# schematic.net
KiCad netlist of a schematic drawn in EAGLE
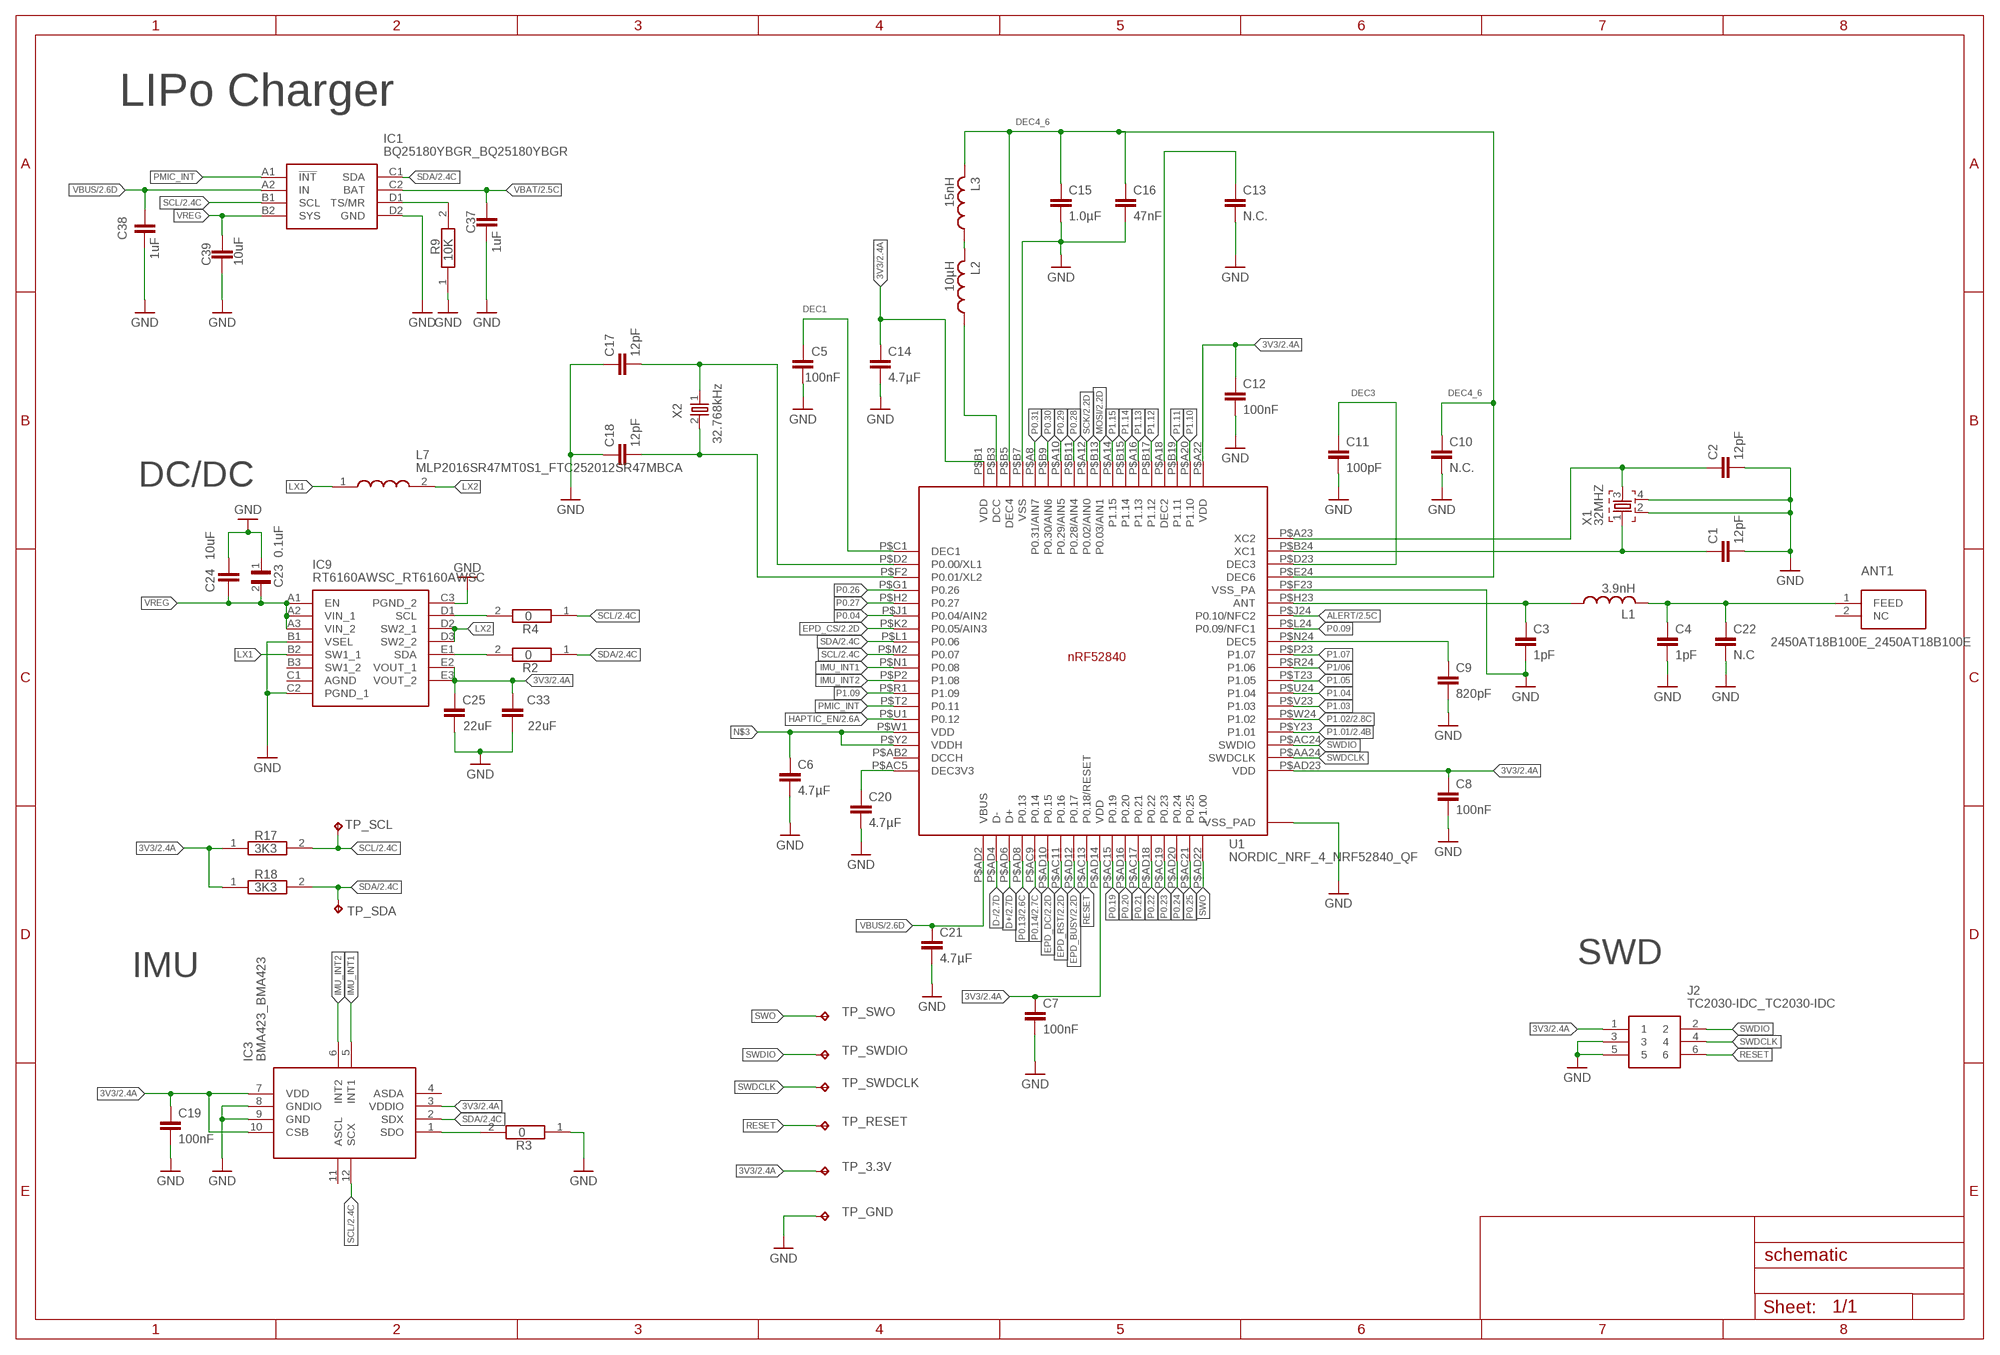
[diagram p0: schematic, sheet 1, part 1 of 2]
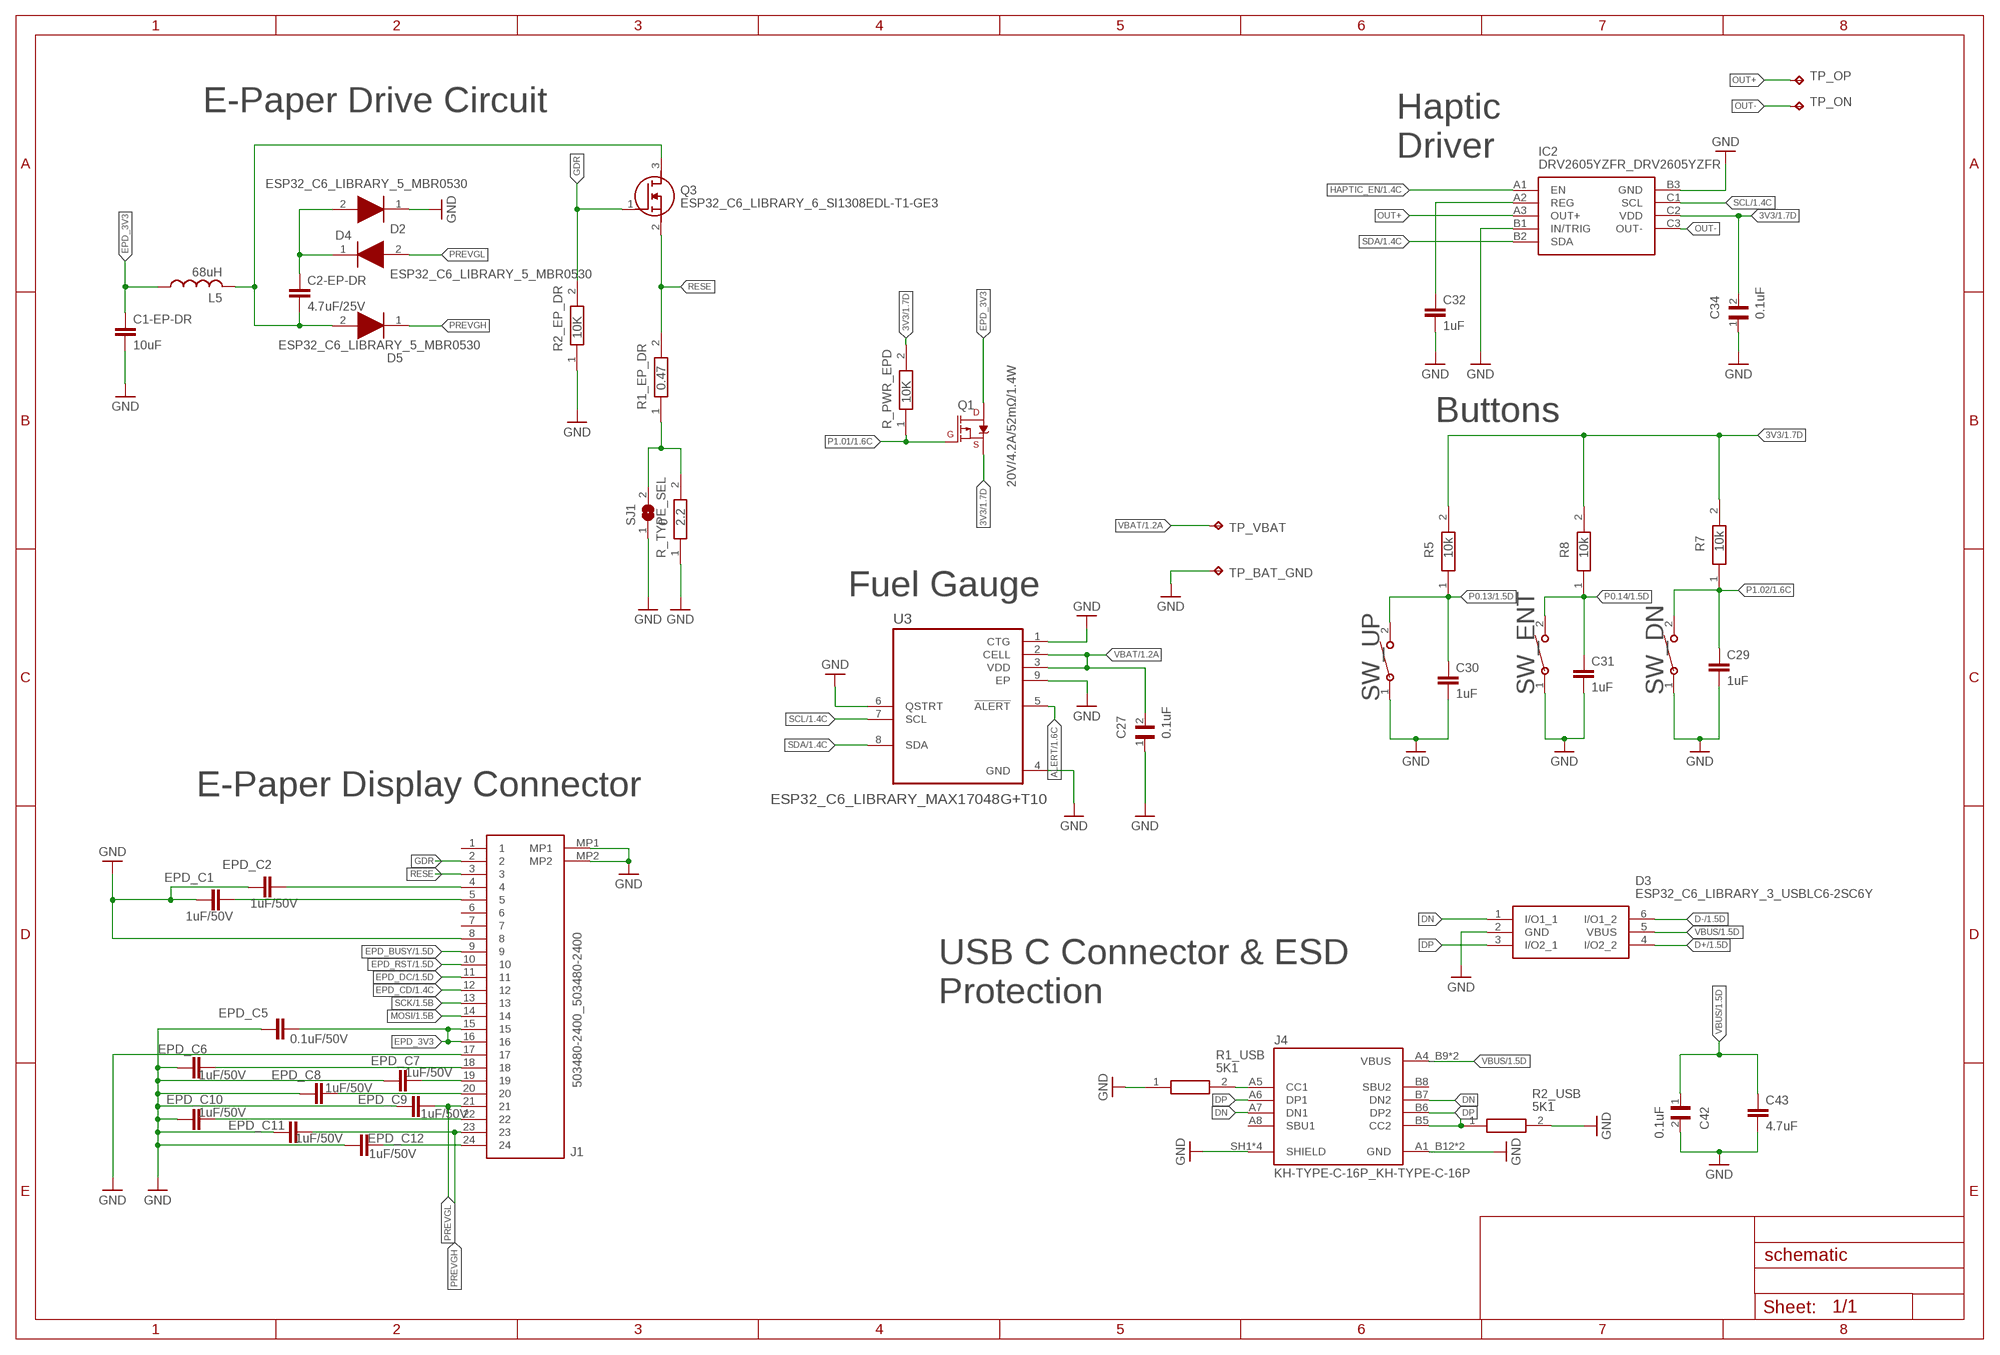
[diagram p1: schematic, sheet 1, part 2 of 2]

(export (version "E")
  (design (tool "Eeschema 10.0.6"))
  (components
    (comp (ref "ANT1")
      (value "2450AT18B100E_2450AT18B100E")
      (footprint "eagle-import:2450AT18B100E_ANTC3216X140N")
      (fields
        (field (name "ARROW_PART_NUMBER") "2450AT18B100E")
        (field (name "MOUSER_PART_NUMBER") "609-2450AT18B100E")
      )
      (libsource (lib "eagle-import") (part "2450AT18B100E_2450AT18B100E"))
    )
    (comp (ref "C1")
      (value "12pF")
      (footprint "eagle-import:NORDIC_NRF_3_RESC0201_L")
      (libsource (lib "eagle-import") (part "NORDIC_NRF_3_CAPACITOR_0201_L"))
    )
    (comp (ref "C1-EP-DR")
      (value "10uF")
      (footprint "eagle-import:PERFECT_0402_0402")
      (libsource (lib "eagle-import") (part "PERFECT_0402_CAP_0402"))
    )
    (comp (ref "C2")
      (value "12pF")
      (footprint "eagle-import:NORDIC_NRF_3_RESC0201_L")
      (libsource (lib "eagle-import") (part "NORDIC_NRF_3_CAPACITOR_0201_L"))
    )
    (comp (ref "C2-EP-DR")
      (value "4.7uF/25V")
      (footprint "eagle-import:PERFECT_0402_0402")
      (libsource (lib "eagle-import") (part "PERFECT_0402_CAP_0402"))
    )
    (comp (ref "C3")
      (value "1pF")
      (footprint "eagle-import:NORDIC_NRF_3_RESC0201_L")
      (libsource (lib "eagle-import") (part "NORDIC_NRF_3_CAPACITOR_0201_L"))
    )
    (comp (ref "C4")
      (value "1pF")
      (footprint "eagle-import:NORDIC_NRF_3_RESC0201_L")
      (libsource (lib "eagle-import") (part "NORDIC_NRF_3_CAPACITOR_0201_L"))
    )
    (comp (ref "C5")
      (value "100nF")
      (footprint "eagle-import:NORDIC_NRF_3_RESC0201_L")
      (libsource (lib "eagle-import") (part "NORDIC_NRF_3_CAPACITOR_0201_L"))
    )
    (comp (ref "C6")
      (value "4.7µF")
      (footprint "eagle-import:PERFECT_0402_0402")
      (libsource (lib "eagle-import") (part "PERFECT_0402_CAP_0402"))
    )
    (comp (ref "C7")
      (value "100nF")
      (footprint "eagle-import:PERFECT_0402_0402")
      (libsource (lib "eagle-import") (part "PERFECT_0402_CAP_0402"))
    )
    (comp (ref "C8")
      (value "100nF")
      (footprint "eagle-import:NORDIC_NRF_3_RESC0201_L")
      (libsource (lib "eagle-import") (part "NORDIC_NRF_3_CAPACITOR_0201_L"))
    )
    (comp (ref "C9")
      (value "820pF")
      (footprint "eagle-import:NORDIC_NRF_3_RESC0201_L")
      (libsource (lib "eagle-import") (part "NORDIC_NRF_3_CAPACITOR_0201_L"))
    )
    (comp (ref "C10")
      (value "N.C.")
      (footprint "eagle-import:NORDIC_NRF_3_RESC0201_L")
      (libsource (lib "eagle-import") (part "NORDIC_NRF_3_CAPACITOR_0201_L"))
    )
    (comp (ref "C11")
      (value "100pF")
      (footprint "eagle-import:NORDIC_NRF_3_RESC0201_L")
      (libsource (lib "eagle-import") (part "NORDIC_NRF_3_CAPACITOR_0201_L"))
    )
    (comp (ref "C12")
      (value "100nF")
      (footprint "eagle-import:NORDIC_NRF_3_RESC0201_L")
      (libsource (lib "eagle-import") (part "NORDIC_NRF_3_CAPACITOR_0201_L"))
    )
    (comp (ref "C13")
      (value "N.C.")
      (footprint "eagle-import:PERFECT_0402_0402")
      (libsource (lib "eagle-import") (part "PERFECT_0402_CAP_0402"))
    )
    (comp (ref "C14")
      (value "4.7µF")
      (footprint "eagle-import:PERFECT_0402_0402")
      (libsource (lib "eagle-import") (part "PERFECT_0402_CAP_0402"))
    )
    (comp (ref "C15")
      (value "1.0µF")
      (footprint "eagle-import:PERFECT_0402_0402")
      (libsource (lib "eagle-import") (part "PERFECT_0402_CAP_0402"))
    )
    (comp (ref "C16")
      (value "47nF")
      (footprint "eagle-import:NORDIC_NRF_3_RESC0201_L")
      (libsource (lib "eagle-import") (part "NORDIC_NRF_3_CAPACITOR_0201_L"))
    )
    (comp (ref "C17")
      (value "12pF")
      (footprint "eagle-import:NORDIC_NRF_3_RESC0201_L")
      (libsource (lib "eagle-import") (part "NORDIC_NRF_3_CAPACITOR_0201_L"))
    )
    (comp (ref "C18")
      (value "12pF")
      (footprint "eagle-import:NORDIC_NRF_3_RESC0201_L")
      (libsource (lib "eagle-import") (part "NORDIC_NRF_3_CAPACITOR_0201_L"))
    )
    (comp (ref "C19")
      (value "100nF")
      (footprint "eagle-import:NORDIC_NRF_3_RESC0201_L")
      (libsource (lib "eagle-import") (part "NORDIC_NRF_3_CAPACITOR_0201_L"))
    )
    (comp (ref "C20")
      (value "4.7µF")
      (footprint "eagle-import:PERFECT_0402_0402")
      (libsource (lib "eagle-import") (part "PERFECT_0402_CAP_0402"))
    )
    (comp (ref "C21")
      (value "4.7µF")
      (footprint "eagle-import:PERFECT_0402_0402")
      (libsource (lib "eagle-import") (part "PERFECT_0402_CAP_0402"))
    )
    (comp (ref "C22")
      (value "N.C")
      (footprint "eagle-import:NORDIC_NRF_3_RESC0201_L")
      (libsource (lib "eagle-import") (part "NORDIC_NRF_3_CAPACITOR_0201_L"))
    )
    (comp (ref "C23")
      (value "0.1uF")
      (footprint "eagle-import:GRM011R60J152KE01L_2_CAPC0201X13N")
      (fields (field (name "MF") "Murata") (field (name "MP") "GRM011R60J152KE01L"))
      (libsource (lib "eagle-import") (part "GRM011R60J152KE01L_2_GRM011R60J152KE01L"))
    )
    (comp (ref "C24")
      (value "10uF")
      (footprint "eagle-import:PERFECT_0402_0402")
      (libsource (lib "eagle-import") (part "PERFECT_0402_CAP_0402"))
    )
    (comp (ref "C25")
      (value "22uF")
      (footprint "eagle-import:PERFECT_0402_0402")
      (libsource (lib "eagle-import") (part "PERFECT_0402_CAP_0402"))
    )
    (comp (ref "C27")
      (value "0.1uF")
      (footprint "eagle-import:GRM011R60J152KE01L_2_CAPC0201X13N")
      (fields (field (name "MF") "Murata") (field (name "MP") "GRM011R60J152KE01L"))
      (libsource (lib "eagle-import") (part "GRM011R60J152KE01L_2_GRM011R60J152KE01L"))
    )
    (comp (ref "C29")
      (value "1uF")
      (footprint "eagle-import:PERFECT_0402_0402")
      (libsource (lib "eagle-import") (part "PERFECT_0402_CAP_0402"))
    )
    (comp (ref "C30")
      (value "1uF")
      (footprint "eagle-import:PERFECT_0402_0402")
      (libsource (lib "eagle-import") (part "PERFECT_0402_CAP_0402"))
    )
    (comp (ref "C31")
      (value "1uF")
      (footprint "eagle-import:PERFECT_0402_0402")
      (libsource (lib "eagle-import") (part "PERFECT_0402_CAP_0402"))
    )
    (comp (ref "C32")
      (value "1uF")
      (footprint "eagle-import:PERFECT_0402_0402")
      (libsource (lib "eagle-import") (part "PERFECT_0402_CAP_0402"))
    )
    (comp (ref "C33")
      (value "22uF")
      (footprint "eagle-import:PERFECT_0402_0402")
      (libsource (lib "eagle-import") (part "PERFECT_0402_CAP_0402"))
    )
    (comp (ref "C34")
      (value "0.1uF")
      (footprint "eagle-import:GRM011R60J152KE01L_2_CAPC0201X13N")
      (fields (field (name "MF") "Murata") (field (name "MP") "GRM011R60J152KE01L"))
      (libsource (lib "eagle-import") (part "GRM011R60J152KE01L_2_GRM011R60J152KE01L"))
    )
    (comp (ref "C37")
      (value "1uF")
      (footprint "eagle-import:PERFECT_0402_0402")
      (libsource (lib "eagle-import") (part "PERFECT_0402_CAP_0402"))
    )
    (comp (ref "C38")
      (value "1uF")
      (footprint "eagle-import:PERFECT_0402_0402")
      (libsource (lib "eagle-import") (part "PERFECT_0402_CAP_0402"))
    )
    (comp (ref "C39")
      (value "10uF")
      (footprint "eagle-import:PERFECT_0402_0402")
      (libsource (lib "eagle-import") (part "PERFECT_0402_CAP_0402"))
    )
    (comp (ref "C42")
      (value "0.1uF")
      (footprint "eagle-import:GRM011R60J152KE01L_2_CAPC0201X13N")
      (fields (field (name "MF") "Murata") (field (name "MP") "GRM011R60J152KE01L"))
      (libsource (lib "eagle-import") (part "GRM011R60J152KE01L_2_GRM011R60J152KE01L"))
    )
    (comp (ref "C43")
      (value "4.7uF")
      (footprint "eagle-import:PERFECT_0402_0402")
      (libsource (lib "eagle-import") (part "PERFECT_0402_CAP_0402"))
    )
    (comp (ref "D2")
      (value "ESP32_C6_LIBRARY_5_MBR0530")
      (footprint "eagle-import:ESP32_C6_LIBRARY_5_SOD3716X135N")
      (fields (field (name "MF") "ON Semiconductor") (field (name "MP") "MBR0530"))
      (libsource (lib "eagle-import") (part "ESP32_C6_LIBRARY_5_MBR0530"))
    )
    (comp (ref "D3")
      (value "ESP32_C6_LIBRARY_3_USBLC6-2SC6Y")
      (footprint "eagle-import:ESP32_C6_LIBRARY_3_SOT95P280X145-6N")
      (fields (field (name "MF") "STMicroelectronics") (field (name "MP") "USBLC6-2SC6Y"))
      (libsource (lib "eagle-import") (part "ESP32_C6_LIBRARY_3_USBLC6-2SC6Y"))
    )
    (comp (ref "D4")
      (value "ESP32_C6_LIBRARY_5_MBR0530")
      (footprint "eagle-import:ESP32_C6_LIBRARY_5_SOD3716X135N")
      (fields (field (name "MF") "ON Semiconductor") (field (name "MP") "MBR0530"))
      (libsource (lib "eagle-import") (part "ESP32_C6_LIBRARY_5_MBR0530"))
    )
    (comp (ref "D5")
      (value "ESP32_C6_LIBRARY_5_MBR0530")
      (footprint "eagle-import:ESP32_C6_LIBRARY_5_SOD3716X135N")
      (fields (field (name "MF") "ON Semiconductor") (field (name "MP") "MBR0530"))
      (libsource (lib "eagle-import") (part "ESP32_C6_LIBRARY_5_MBR0530"))
    )
    (comp (ref "EPD_C1")
      (value "1uF/50V")
      (footprint "eagle-import:PERFECT_0402_0402")
      (libsource (lib "eagle-import") (part "PERFECT_0402_CAP_0402"))
    )
    (comp (ref "EPD_C2")
      (value "1uF/50V")
      (footprint "eagle-import:PERFECT_0402_0402")
      (libsource (lib "eagle-import") (part "PERFECT_0402_CAP_0402"))
    )
    (comp (ref "EPD_C5")
      (value "0.1uF/50V")
      (footprint "eagle-import:NORDIC_NRF_3_RESC0201_L")
      (libsource (lib "eagle-import") (part "NORDIC_NRF_3_CAPACITOR_0201_L"))
    )
    (comp (ref "EPD_C6")
      (value "1uF/50V")
      (footprint "eagle-import:PERFECT_0402_0402")
      (libsource (lib "eagle-import") (part "PERFECT_0402_CAP_0402"))
    )
    (comp (ref "EPD_C7")
      (value "1uF/50V")
      (footprint "eagle-import:PERFECT_0402_0402")
      (libsource (lib "eagle-import") (part "PERFECT_0402_CAP_0402"))
    )
    (comp (ref "EPD_C8")
      (value "1uF/50V")
      (footprint "eagle-import:PERFECT_0402_0402")
      (libsource (lib "eagle-import") (part "PERFECT_0402_CAP_0402"))
    )
    (comp (ref "EPD_C9")
      (value "1uF/50V")
      (footprint "eagle-import:PERFECT_0402_0402")
      (libsource (lib "eagle-import") (part "PERFECT_0402_CAP_0402"))
    )
    (comp (ref "EPD_C10")
      (value "1uF/50V")
      (footprint "eagle-import:PERFECT_0402_0402")
      (libsource (lib "eagle-import") (part "PERFECT_0402_CAP_0402"))
    )
    (comp (ref "EPD_C11")
      (value "1uF/50V")
      (footprint "eagle-import:PERFECT_0402_0402")
      (libsource (lib "eagle-import") (part "PERFECT_0402_CAP_0402"))
    )
    (comp (ref "EPD_C12")
      (value "1uF/50V")
      (footprint "eagle-import:PERFECT_0402_0402")
      (libsource (lib "eagle-import") (part "PERFECT_0402_CAP_0402"))
    )
    (comp (ref "IC1")
      (value "BQ25180YBGR_BQ25180YBGR")
      (footprint "eagle-import:BQ25180YBGR_BGA8C40P2X4_100X155X50")
      (fields
        (field (name "ARROW_PART_NUMBER") "BQ25180YBGR")
        (field (name "MOUSER_PART_NUMBER") "595-BQ25180YBGR")
      )
      (libsource (lib "eagle-import") (part "BQ25180YBGR_BQ25180YBGR"))
    )
    (comp (ref "IC2")
      (value "DRV2605YZFR_DRV2605YZFR")
      (footprint "eagle-import:DRV2605YZFR_BGA9C50P3X3_144X144X62")
      (fields (field (name "ARROW_PART_NUMBER") "DRV2605YZFR"))
      (libsource (lib "eagle-import") (part "DRV2605YZFR_DRV2605YZFR"))
    )
    (comp (ref "IC3")
      (value "BMA423_BMA423")
      (footprint "eagle-import:BMA423_BMA423")
      (fields (field (name "ARROW_PART_NUMBER") "BMA423") (field (name "MOUSER_PART_NUMBER") "262-BMA423"))
      (libsource (lib "eagle-import") (part "BMA423_BMA423"))
    )
    (comp (ref "IC9")
      (value "RT6160AWSC_RT6160AWSC")
      (footprint "eagle-import:RT6160AWSC_BGA15C40P3X5_140X230X60")
      (fields
        (field (name "MANUFACTURER_PART_NUMBER") "RT6160AWSC")
        (field (name "MOUSER_PART_NUMBER") "835-RT6160AWSC")
      )
      (libsource (lib "eagle-import") (part "RT6160AWSC_RT6160AWSC"))
    )
    (comp (ref "J1")
      (value "503480-2400_503480-2400")
      (footprint "eagle-import:503480-2400_5034802400")
      (fields
        (field (name "MANUFACTURER_PART_NUMBER") "503480-2400")
        (field (name "MOUSER_PART_NUMBER") "538-503480-2400")
      )
      (libsource (lib "eagle-import") (part "503480-2400_503480-2400"))
    )
    (comp (ref "J2")
      (value "TC2030-IDC_TC2030-IDC")
      (footprint "eagle-import:TC2030-IDC_TC2030IDC")
      (fields (field (name "MANUFACTURER_PART_NUMBER") "TC2030-IDC"))
      (libsource (lib "eagle-import") (part "TC2030-IDC_TC2030-IDC"))
    )
    (comp (ref "J4")
      (value "KH-TYPE-C-16P_KH-TYPE-C-16P")
      (footprint "eagle-import:KH-TYPE-C-16P_KINGHELM_KH-TYPE-C-16P")
      (fields (field (name "MF") "kinghelm") (field (name "MP") "KH-TYPE-C-16P"))
      (libsource (lib "eagle-import") (part "KH-TYPE-C-16P_KH-TYPE-C-16P"))
    )
    (comp (ref "L1")
      (value "3.9nH")
      (footprint "eagle-import:NORDIC_NRF_2_RESC0402_L")
      (libsource (lib "eagle-import") (part "NORDIC_NRF_2_INDUCTOR_0402_L"))
    )
    (comp (ref "L2")
      (value "10µH")
      (footprint "eagle-import:NORDIC_NRF_2_RESC0402_L")
      (libsource (lib "eagle-import") (part "NORDIC_NRF_2_INDUCTOR_0402_L"))
    )
    (comp (ref "L3")
      (value "15nH")
      (footprint "eagle-import:NORDIC_NRF_2_RESC0402_L")
      (libsource (lib "eagle-import") (part "NORDIC_NRF_2_INDUCTOR_0402_L"))
    )
    (comp (ref "L5")
      (value "68uH")
      (footprint "eagle-import:NORDIC_NRF_2_RESC0402_L")
      (libsource (lib "eagle-import") (part "NORDIC_NRF_2_INDUCTOR_0402_L"))
    )
    (comp (ref "L7")
      (value "MLP2016SR47MT0S1_FTC252012SR47MBCA")
      (footprint "eagle-import:MLP2016SR47MT0S1_INDC2016X100N")
      (fields (field (name "MANUFACTURER_PART_NUMBER") "FTC252012SR47MBCA"))
      (libsource (lib "eagle-import") (part "MLP2016SR47MT0S1_FTC252012SR47MBCA"))
    )
    (comp (ref "Q1")
      (value "20V/4.2A/52mΩ/1.4W")
      (footprint "eagle-import:ESP32_C6_LIBRARY_4_ESP32_C6_LIBRARY_4_ESP32_C6_LIBRARY_4_ESP32_C6_LIBRARY_4_ESP32_WROVER_SPARKFUN-DISCRETESEMI_SOT23-3")
      (libsource (lib "eagle-import") (part "ESP32_C6_LIBRARY_4_ESP32_WROVER_SPARKFUN-DISCRETESEMI_MOSFET_PCH-DMG2305UX-7"))
    )
    (comp (ref "Q3")
      (value "ESP32_C6_LIBRARY_6_SI1308EDL-T1-GE3")
      (footprint "eagle-import:ESP32_C6_LIBRARY_6_SOT65P210X110-3N")
      (fields (field (name "MF") "Vishay Siliconix") (field (name "MP") "SI1308EDL-T1-GE3"))
      (libsource (lib "eagle-import") (part "ESP32_C6_LIBRARY_6_SI1308EDL-T1-GE3"))
    )
    (comp (ref "R1_EP_DR")
      (value "0.47")
      (footprint "eagle-import:CPF0201D7K68C1_0201")
      (libsource (lib "eagle-import") (part "CPF0201D7K68C1_CPF0201D7K68C1"))
    )
    (comp (ref "R1_USB")
      (value "5K1")
      (footprint "eagle-import:CPF0201D7K68C1_0201")
      (libsource (lib "eagle-import") (part "CPF0201D7K68C1_CPF0201D7K68C1"))
    )
    (comp (ref "R2")
      (value "0")
      (footprint "eagle-import:ERA-1AEB3401C_0201")
      (libsource (lib "eagle-import") (part "ERA-1AEB3401C_CPF0201D7K68C1"))
    )
    (comp (ref "R2_EP_DR")
      (value "10K")
      (footprint "eagle-import:CPF0201D7K68C1_0201")
      (libsource (lib "eagle-import") (part "CPF0201D7K68C1_CPF0201D7K68C1"))
    )
    (comp (ref "R2_USB")
      (value "5K1")
      (footprint "eagle-import:CPF0201D7K68C1_0201")
      (libsource (lib "eagle-import") (part "CPF0201D7K68C1_CPF0201D7K68C1"))
    )
    (comp (ref "R3")
      (value "0")
      (footprint "eagle-import:ERA-1AEB3401C_0201")
      (libsource (lib "eagle-import") (part "ERA-1AEB3401C_CPF0201D7K68C1"))
    )
    (comp (ref "R4")
      (value "0")
      (footprint "eagle-import:ERA-1AEB3401C_0201")
      (libsource (lib "eagle-import") (part "ERA-1AEB3401C_CPF0201D7K68C1"))
    )
    (comp (ref "R5")
      (value "10k")
      (footprint "eagle-import:CPF0201D7K68C1_0201")
      (libsource (lib "eagle-import") (part "CPF0201D7K68C1_CPF0201D7K68C1"))
    )
    (comp (ref "R7")
      (value "10k")
      (footprint "eagle-import:CPF0201D7K68C1_0201")
      (libsource (lib "eagle-import") (part "CPF0201D7K68C1_CPF0201D7K68C1"))
    )
    (comp (ref "R8")
      (value "10k")
      (footprint "eagle-import:CPF0201D7K68C1_0201")
      (libsource (lib "eagle-import") (part "CPF0201D7K68C1_CPF0201D7K68C1"))
    )
    (comp (ref "R9")
      (value "10K")
      (footprint "eagle-import:CPF0201D7K68C1_0201")
      (libsource (lib "eagle-import") (part "CPF0201D7K68C1_CPF0201D7K68C1"))
    )
    (comp (ref "R17")
      (value "3K3")
      (footprint "eagle-import:ERA-1AEB3401C_0201")
      (libsource (lib "eagle-import") (part "ERA-1AEB3401C_CPF0201D7K68C1"))
    )
    (comp (ref "R18")
      (value "3K3")
      (footprint "eagle-import:ERA-1AEB3401C_0201")
      (libsource (lib "eagle-import") (part "ERA-1AEB3401C_CPF0201D7K68C1"))
    )
    (comp (ref "R_PWR_EPD")
      (value "10K")
      (footprint "eagle-import:CPF0201D7K68C1_0201")
      (libsource (lib "eagle-import") (part "CPF0201D7K68C1_CPF0201D7K68C1"))
    )
    (comp (ref "R_TYPE_SEL")
      (value "2.2")
      (footprint "eagle-import:CPF0201D7K68C1_0201")
      (libsource (lib "eagle-import") (part "CPF0201D7K68C1_CPF0201D7K68C1"))
    )
    (comp (ref "SJ1")
      (value "0")
      (footprint "eagle-import:ESP32_C6_LIBRARY_7_JUMPER_SJ")
      (libsource (lib "eagle-import") (part "ESP32_C6_LIBRARY_7_JUMPER_SJ"))
    )
    (comp (ref "SW_DN")
      (value "2025-10-22_07-23-44_LIBRARY_EVP-AKE31ASW_EVP-AKE31A_PAN")
      (footprint "eagle-import:2025-10-22_07-23-44_LIBRARY_SW_EVP-AKE31A_PAN")
      (fields
        (field (name "MANUFACTURER_PART_NUMBER") "EVP-AKE31A")
        (field (name "COPYRIGHT") "Copyright (C) 2025 Ultra Librarian. All rights reserved.")
      )
      (libsource (lib "eagle-import") (part "2025-10-22_07-23-44_LIBRARY_EVP-AKE31ASW_EVP-AKE31A_PAN"))
    )
    (comp (ref "SW_ENT")
      (value "2025-10-22_07-23-44_LIBRARY_EVP-AKE31ASW_EVP-AKE31A_PAN")
      (footprint "eagle-import:2025-10-22_07-23-44_LIBRARY_SW_EVP-AKE31A_PAN")
      (fields
        (field (name "MANUFACTURER_PART_NUMBER") "EVP-AKE31A")
        (field (name "COPYRIGHT") "Copyright (C) 2025 Ultra Librarian. All rights reserved.")
      )
      (libsource (lib "eagle-import") (part "2025-10-22_07-23-44_LIBRARY_EVP-AKE31ASW_EVP-AKE31A_PAN"))
    )
    (comp (ref "SW_UP")
      (value "2025-10-22_07-23-44_LIBRARY_EVP-AKE31ASW_EVP-AKE31A_PAN")
      (footprint "eagle-import:2025-10-22_07-23-44_LIBRARY_SW_EVP-AKE31A_PAN")
      (fields
        (field (name "MANUFACTURER_PART_NUMBER") "EVP-AKE31A")
        (field (name "COPYRIGHT") "Copyright (C) 2025 Ultra Librarian. All rights reserved.")
      )
      (libsource (lib "eagle-import") (part "2025-10-22_07-23-44_LIBRARY_EVP-AKE31ASW_EVP-AKE31A_PAN"))
    )
    (comp (ref "TP_3.3V")
      (value "HECTOR_WATCH_1_TPTP20R")
      (footprint "eagle-import:HECTOR_WATCH_1_TP20R")
      (libsource (lib "eagle-import") (part "HECTOR_WATCH_1_TPTP20R"))
    )
    (comp (ref "TP_BAT_GND")
      (value "HECTOR_WATCH_1_TPTP20R")
      (footprint "eagle-import:HECTOR_WATCH_1_TP20R")
      (libsource (lib "eagle-import") (part "HECTOR_WATCH_1_TPTP20R"))
    )
    (comp (ref "TP_GND")
      (value "HECTOR_WATCH_1_TPTP20R")
      (footprint "eagle-import:HECTOR_WATCH_1_TP20R")
      (libsource (lib "eagle-import") (part "HECTOR_WATCH_1_TPTP20R"))
    )
    (comp (ref "TP_ON")
      (value "HECTOR_WATCH_1_TPTP20R")
      (footprint "eagle-import:HECTOR_WATCH_1_TP20R")
      (libsource (lib "eagle-import") (part "HECTOR_WATCH_1_TPTP20R"))
    )
    (comp (ref "TP_OP")
      (value "HECTOR_WATCH_1_TPTP20R")
      (footprint "eagle-import:HECTOR_WATCH_1_TP20R")
      (libsource (lib "eagle-import") (part "HECTOR_WATCH_1_TPTP20R"))
    )
    (comp (ref "TP_RESET")
      (value "HECTOR_WATCH_1_TPTP20R")
      (footprint "eagle-import:HECTOR_WATCH_1_TP20R")
      (libsource (lib "eagle-import") (part "HECTOR_WATCH_1_TPTP20R"))
    )
    (comp (ref "TP_SCL")
      (value "HECTOR_WATCH_1_TPTP20R")
      (footprint "eagle-import:HECTOR_WATCH_1_TP20R")
      (libsource (lib "eagle-import") (part "HECTOR_WATCH_1_TPTP20R"))
    )
    (comp (ref "TP_SDA")
      (value "HECTOR_WATCH_1_TPTP20R")
      (footprint "eagle-import:HECTOR_WATCH_1_TP20R")
      (libsource (lib "eagle-import") (part "HECTOR_WATCH_1_TPTP20R"))
    )
    (comp (ref "TP_SWDCLK")
      (value "HECTOR_WATCH_1_TPTP20R")
      (footprint "eagle-import:HECTOR_WATCH_1_TP20R")
      (libsource (lib "eagle-import") (part "HECTOR_WATCH_1_TPTP20R"))
    )
    (comp (ref "TP_SWDIO")
      (value "HECTOR_WATCH_1_TPTP20R")
      (footprint "eagle-import:HECTOR_WATCH_1_TP20R")
      (libsource (lib "eagle-import") (part "HECTOR_WATCH_1_TPTP20R"))
    )
    (comp (ref "TP_SWO")
      (value "HECTOR_WATCH_1_TPTP20R")
      (footprint "eagle-import:HECTOR_WATCH_1_TP20R")
      (libsource (lib "eagle-import") (part "HECTOR_WATCH_1_TPTP20R"))
    )
    (comp (ref "TP_VBAT")
      (value "HECTOR_WATCH_1_TPTP20R")
      (footprint "eagle-import:HECTOR_WATCH_1_TP20R")
      (libsource (lib "eagle-import") (part "HECTOR_WATCH_1_TPTP20R"))
    )
    (comp (ref "U1")
      (value "NORDIC_NRF_4_NRF52840_QF")
      (footprint "eagle-import:NORDIC_NRF_4_AQFN50P700X700X85_HS-74N")
      (libsource (lib "eagle-import") (part "NORDIC_NRF_4_NRF52840_QF"))
    )
    (comp (ref "U3")
      (value "ESP32_C6_LIBRARY_MAX17048G+T10")
      (footprint "eagle-import:ESP32_C6_LIBRARY_SON50P200X200X80-9N")
      (fields (field (name "MF") "Analog Devices") (field (name "MP") "MAX17048G+T10"))
      (libsource (lib "eagle-import") (part "ESP32_C6_LIBRARY_MAX17048G+T10"))
    )
    (comp (ref "X1")
      (value "32MHZ")
      (footprint "eagle-import:NORDIC_NRF_BT-XTAL_2016_N")
      (libsource (lib "eagle-import") (part "NORDIC_NRF_XTAL_32MHZ"))
    )
    (comp (ref "X2")
      (value "32.768kHz")
      (footprint "eagle-import:NORDIC_NRF_1_XTAL_3215_N")
      (libsource (lib "eagle-import") (part "NORDIC_NRF_1_XTAL_32KHZ"))
    )
  )
  (nets
    (net (code "1") (name "3V3{slash}1.7D") (class "Default")
      (node (ref "C34") (pin "2") (pinfunction "2_2") (pintype "passive"))
      (node (ref "IC2") (pin "C2") (pinfunction "VDD_C2") (pintype "bidirectional"))
      (node (ref "Q1") (pin "2") (pinfunction "S_2") (pintype "bidirectional"))
      (node (ref "R5") (pin "2") (pinfunction "2_2") (pintype "bidirectional"))
      (node (ref "R7") (pin "2") (pinfunction "2_2") (pintype "bidirectional"))
      (node (ref "R8") (pin "2") (pinfunction "2_2") (pintype "bidirectional"))
      (node (ref "R_PWR_EPD") (pin "2") (pinfunction "2_2") (pintype "bidirectional"))
    )
    (net (code "2") (name "3V3{slash}2.4A") (class "Default")
      (node (ref "C12") (pin "1") (pinfunction "1_1") (pintype "passive"))
      (node (ref "C14") (pin "1") (pinfunction "1_1") (pintype "passive"))
      (node (ref "C19") (pin "1") (pinfunction "1_1") (pintype "passive"))
      (node (ref "C25") (pin "2") (pinfunction "2_2") (pintype "passive"))
      (node (ref "C33") (pin "2") (pinfunction "2_2") (pintype "passive"))
      (node (ref "C7") (pin "1") (pinfunction "1_1") (pintype "passive"))
      (node (ref "C8") (pin "1") (pinfunction "1_1") (pintype "passive"))
      (node (ref "IC3") (pin "10") (pinfunction "CSB_10") (pintype "bidirectional"))
      (node (ref "IC3") (pin "3") (pinfunction "VDDIO_3") (pintype "bidirectional"))
      (node (ref "IC3") (pin "7") (pinfunction "VDD_7") (pintype "bidirectional"))
      (node (ref "IC9") (pin "E2") (pinfunction "VOUT_1_E2") (pintype "bidirectional"))
      (node (ref "IC9") (pin "E3") (pinfunction "VOUT_2_E3") (pintype "bidirectional"))
      (node (ref "J2") (pin "1") (pinfunction "1_1") (pintype "bidirectional"))
      (node (ref "R17") (pin "1") (pinfunction "1_1") (pintype "bidirectional"))
      (node (ref "R18") (pin "1") (pinfunction "1_1") (pintype "bidirectional"))
      (node (ref "TP_3.3V") (pin "TP") (pinfunction "TP_TP") (pintype "input"))
      (node (ref "U1") (pin "P$A22") (pinfunction "VDD_P$A22") (pintype "power_in"))
      (node (ref "U1") (pin "P$AD14") (pinfunction "VDD_P$AD14") (pintype "power_in"))
      (node (ref "U1") (pin "P$AD23") (pinfunction "VDD_P$AD23") (pintype "power_in"))
      (node (ref "U1") (pin "P$B1") (pinfunction "VDD_P$B1") (pintype "power_in"))
    )
    (net (code "3") (name "ALERT{slash}1.6C") (class "Default")
      (node (ref "U3") (pin "5") (pinfunction "~{ALERT}_5") (pintype "output"))
    )
    (net (code "4") (name "ALERT{slash}2.5C") (class "Default")
      (node (ref "U1") (pin "P$J24") (pinfunction "P0.10/NFC2_P$J24") (pintype "bidirectional"))
    )
    (net (code "5") (name "D+{slash}1.5D") (class "Default")
      (node (ref "D3") (pin "4") (pinfunction "I/O2_2_4") (pintype "bidirectional"))
    )
    (net (code "6") (name "D+{slash}2.7D") (class "Default")
      (node (ref "U1") (pin "P$AD6") (pinfunction "D+_P$AD6") (pintype "bidirectional"))
    )
    (net (code "7") (name "D-{slash}1.5D") (class "Default")
      (node (ref "D3") (pin "6") (pinfunction "I/O1_2_6") (pintype "bidirectional"))
    )
    (net (code "8") (name "D-{slash}2.7D") (class "Default")
      (node (ref "U1") (pin "P$AD4") (pinfunction "D-_P$AD4") (pintype "bidirectional"))
    )
    (net (code "9") (name "DN") (class "Default")
      (node (ref "D3") (pin "1") (pinfunction "I/O1_1_1") (pintype "bidirectional"))
      (node (ref "J4") (pin "A7") (pinfunction "DN1_A7") (pintype "bidirectional"))
      (node (ref "J4") (pin "B7") (pinfunction "DN2_B7") (pintype "bidirectional"))
    )
    (net (code "10") (name "DP") (class "Default")
      (node (ref "D3") (pin "3") (pinfunction "I/O2_1_3") (pintype "bidirectional"))
      (node (ref "J4") (pin "A6") (pinfunction "DP1_A6") (pintype "bidirectional"))
      (node (ref "J4") (pin "B6") (pinfunction "DP2_B6") (pintype "bidirectional"))
    )
    (net (code "11") (name "EPD_3V3") (class "Default")
      (node (ref "C1-EP-DR") (pin "1") (pinfunction "1_1") (pintype "passive"))
      (node (ref "EPD_C5") (pin "2") (pinfunction "2_2") (pintype "passive"))
      (node (ref "J1") (pin "15") (pinfunction "15_15") (pintype "bidirectional"))
      (node (ref "J1") (pin "16") (pinfunction "16_16") (pintype "bidirectional"))
      (node (ref "L5") (pin "1") (pinfunction "1_1") (pintype "passive"))
      (node (ref "Q1") (pin "3") (pinfunction "D_3") (pintype "bidirectional"))
    )
    (net (code "12") (name "EPD_BUSY{slash}1.5D") (class "Default")
      (node (ref "J1") (pin "9") (pinfunction "9_9") (pintype "bidirectional"))
    )
    (net (code "13") (name "EPD_BUSY{slash}2.2D") (class "Default")
      (node (ref "U1") (pin "P$AC11") (pinfunction "P0.16_P$AC11") (pintype "bidirectional"))
    )
    (net (code "14") (name "EPD_CD{slash}1.4C") (class "Default")
      (node (ref "J1") (pin "12") (pinfunction "12_12") (pintype "bidirectional"))
    )
    (net (code "15") (name "EPD_CS{slash}2.2D") (class "Default")
      (node (ref "U1") (pin "P$K2") (pinfunction "P0.05/AIN3_P$K2") (pintype "bidirectional"))
    )
    (net (code "16") (name "EPD_DC{slash}1.5D") (class "Default")
      (node (ref "J1") (pin "11") (pinfunction "11_11") (pintype "bidirectional"))
    )
    (net (code "17") (name "EPD_DC{slash}2.2D") (class "Default")
      (node (ref "U1") (pin "P$AD10") (pinfunction "P0.15_P$AD10") (pintype "bidirectional"))
    )
    (net (code "18") (name "EPD_RST{slash}1.5D") (class "Default")
      (node (ref "J1") (pin "10") (pinfunction "10_10") (pintype "bidirectional"))
    )
    (net (code "19") (name "EPD_RST{slash}2.2D") (class "Default")
      (node (ref "U1") (pin "P$AD12") (pinfunction "P0.17_P$AD12") (pintype "bidirectional"))
    )
    (net (code "20") (name "GDR") (class "Default")
      (node (ref "J1") (pin "2") (pinfunction "2_2") (pintype "bidirectional"))
      (node (ref "Q3") (pin "1") (pinfunction "G_1") (pintype "bidirectional"))
      (node (ref "R2_EP_DR") (pin "2") (pinfunction "2_2") (pintype "bidirectional"))
    )
    (net (code "21") (name "GND") (class "Default")
      (node (ref "C1") (pin "2") (pinfunction "2_2") (pintype "passive"))
      (node (ref "C1-EP-DR") (pin "2") (pinfunction "2_2") (pintype "passive"))
      (node (ref "C10") (pin "2") (pinfunction "2_2") (pintype "passive"))
      (node (ref "C11") (pin "2") (pinfunction "2_2") (pintype "passive"))
      (node (ref "C12") (pin "2") (pinfunction "2_2") (pintype "passive"))
      (node (ref "C13") (pin "2") (pinfunction "2_2") (pintype "passive"))
      (node (ref "C14") (pin "2") (pinfunction "2_2") (pintype "passive"))
      (node (ref "C15") (pin "2") (pinfunction "2_2") (pintype "passive"))
      (node (ref "C16") (pin "2") (pinfunction "2_2") (pintype "passive"))
      (node (ref "C17") (pin "1") (pinfunction "1_1") (pintype "passive"))
      (node (ref "C18") (pin "1") (pinfunction "1_1") (pintype "passive"))
      (node (ref "C19") (pin "2") (pinfunction "2_2") (pintype "passive"))
      (node (ref "C2") (pin "2") (pinfunction "2_2") (pintype "passive"))
      (node (ref "C20") (pin "2") (pinfunction "2_2") (pintype "passive"))
      (node (ref "C21") (pin "2") (pinfunction "2_2") (pintype "passive"))
      (node (ref "C22") (pin "2") (pinfunction "2_2") (pintype "passive"))
      (node (ref "C23") (pin "1") (pinfunction "1_1") (pintype "passive"))
      (node (ref "C24") (pin "2") (pinfunction "2_2") (pintype "passive"))
      (node (ref "C25") (pin "1") (pinfunction "1_1") (pintype "passive"))
      (node (ref "C27") (pin "1") (pinfunction "1_1") (pintype "passive"))
      (node (ref "C29") (pin "2") (pinfunction "2_2") (pintype "passive"))
      (node (ref "C3") (pin "2") (pinfunction "2_2") (pintype "passive"))
      (node (ref "C30") (pin "2") (pinfunction "2_2") (pintype "passive"))
      (node (ref "C31") (pin "2") (pinfunction "2_2") (pintype "passive"))
      (node (ref "C32") (pin "2") (pinfunction "2_2") (pintype "passive"))
      (node (ref "C33") (pin "1") (pinfunction "1_1") (pintype "passive"))
      (node (ref "C34") (pin "1") (pinfunction "1_1") (pintype "passive"))
      (node (ref "C37") (pin "2") (pinfunction "2_2") (pintype "passive"))
      (node (ref "C38") (pin "2") (pinfunction "2_2") (pintype "passive"))
      (node (ref "C39") (pin "2") (pinfunction "2_2") (pintype "passive"))
      (node (ref "C4") (pin "2") (pinfunction "2_2") (pintype "passive"))
      (node (ref "C42") (pin "2") (pinfunction "2_2") (pintype "passive"))
      (node (ref "C43") (pin "2") (pinfunction "2_2") (pintype "passive"))
      (node (ref "C5") (pin "1") (pinfunction "1_1") (pintype "passive"))
      (node (ref "C6") (pin "2") (pinfunction "2_2") (pintype "passive"))
      (node (ref "C7") (pin "2") (pinfunction "2_2") (pintype "passive"))
      (node (ref "C8") (pin "2") (pinfunction "2_2") (pintype "passive"))
      (node (ref "C9") (pin "2") (pinfunction "2_2") (pintype "passive"))
      (node (ref "D3") (pin "2") (pinfunction "GND_2") (pintype "bidirectional"))
      (node (ref "D4") (pin "1") (pinfunction "K_1") (pintype "bidirectional"))
      (node (ref "EPD_C1") (pin "1") (pinfunction "1_1") (pintype "passive"))
      (node (ref "EPD_C10") (pin "1") (pinfunction "1_1") (pintype "passive"))
      (node (ref "EPD_C11") (pin "1") (pinfunction "1_1") (pintype "passive"))
      (node (ref "EPD_C12") (pin "1") (pinfunction "1_1") (pintype "passive"))
      (node (ref "EPD_C2") (pin "1") (pinfunction "1_1") (pintype "passive"))
      (node (ref "EPD_C5") (pin "1") (pinfunction "1_1") (pintype "passive"))
      (node (ref "EPD_C6") (pin "1") (pinfunction "1_1") (pintype "passive"))
      (node (ref "EPD_C7") (pin "1") (pinfunction "1_1") (pintype "passive"))
      (node (ref "EPD_C8") (pin "1") (pinfunction "1_1") (pintype "passive"))
      (node (ref "EPD_C9") (pin "1") (pinfunction "1_1") (pintype "passive"))
      (node (ref "IC1") (pin "D2") (pinfunction "GND_D2") (pintype "bidirectional"))
      (node (ref "IC2") (pin "B1") (pinfunction "IN/TRIG_B1") (pintype "bidirectional"))
      (node (ref "IC2") (pin "B3") (pinfunction "GND_B3") (pintype "bidirectional"))
      (node (ref "IC3") (pin "8") (pinfunction "GNDIO_8") (pintype "bidirectional"))
      (node (ref "IC3") (pin "9") (pinfunction "GND_9") (pintype "bidirectional"))
      (node (ref "IC9") (pin "B1") (pinfunction "VSEL_B1") (pintype "bidirectional"))
      (node (ref "IC9") (pin "C2") (pinfunction "PGND_1_C2") (pintype "bidirectional"))
      (node (ref "IC9") (pin "C3") (pinfunction "PGND_2_C3") (pintype "bidirectional"))
      (node (ref "J1") (pin "17") (pinfunction "17_17") (pintype "bidirectional"))
      (node (ref "J1") (pin "8") (pinfunction "8_8") (pintype "bidirectional"))
      (node (ref "J1") (pin "MP1") (pinfunction "MP1_MP1") (pintype "bidirectional"))
      (node (ref "J1") (pin "MP2") (pinfunction "MP2_MP2") (pintype "bidirectional"))
      (node (ref "J2") (pin "3") (pinfunction "3_3") (pintype "bidirectional"))
      (node (ref "J2") (pin "5") (pinfunction "5_5") (pintype "bidirectional"))
      (node (ref "J4") (pin "A12_B1") (pinfunction "GND_A12_B1") (pintype "power_in"))
      (node (ref "J4") (pin "A1_B12") (pinfunction "GND_A1_B12") (pintype "power_in"))
      (node (ref "J4") (pin "SH1") (pinfunction "SHIELD_SH1") (pintype "passive"))
      (node (ref "J4") (pin "SH2") (pinfunction "SHIELD_SH2") (pintype "passive"))
      (node (ref "J4") (pin "SH3") (pinfunction "SHIELD_SH3") (pintype "passive"))
      (node (ref "J4") (pin "SH4") (pinfunction "SHIELD_SH4") (pintype "passive"))
      (node (ref "R1_USB") (pin "1") (pinfunction "1_1") (pintype "bidirectional"))
      (node (ref "R2_EP_DR") (pin "1") (pinfunction "1_1") (pintype "bidirectional"))
      (node (ref "R2_USB") (pin "2") (pinfunction "2_2") (pintype "bidirectional"))
      (node (ref "R3") (pin "1") (pinfunction "1_1") (pintype "bidirectional"))
      (node (ref "R9") (pin "1") (pinfunction "1_1") (pintype "bidirectional"))
      (node (ref "R_TYPE_SEL") (pin "1") (pinfunction "1_1") (pintype "bidirectional"))
      (node (ref "SJ1") (pin "1") (pinfunction "1_1") (pintype "passive"))
      (node (ref "SW_DN") (pin "1") (pinfunction "1_1") (pintype "passive"))
      (node (ref "SW_ENT") (pin "1") (pinfunction "1_1") (pintype "passive"))
      (node (ref "SW_UP") (pin "1") (pinfunction "1_1") (pintype "passive"))
      (node (ref "TP_BAT_GND") (pin "TP") (pinfunction "TP_TP") (pintype "input"))
      (node (ref "TP_GND") (pin "TP") (pinfunction "TP_TP") (pintype "input"))
      (node (ref "U1") (pin "P$74") (pinfunction "VSS_PAD_P$74") (pintype "bidirectional"))
      (node (ref "U1") (pin "P$75") (pinfunction "VSS_PAD_P$75") (pintype "bidirectional"))
      (node (ref "U1") (pin "P$76") (pinfunction "VSS_PAD_P$76") (pintype "bidirectional"))
      (node (ref "U1") (pin "P$77") (pinfunction "VSS_PAD_P$77") (pintype "bidirectional"))
      (node (ref "U1") (pin "P$78") (pinfunction "VSS_PAD_P$78") (pintype "bidirectional"))
      (node (ref "U1") (pin "P$79") (pinfunction "VSS_PAD_P$79") (pintype "bidirectional"))
      (node (ref "U1") (pin "P$80") (pinfunction "VSS_PAD_P$80") (pintype "bidirectional"))
      (node (ref "U1") (pin "P$81") (pinfunction "VSS_PAD_P$81") (pintype "bidirectional"))
      (node (ref "U1") (pin "P$82") (pinfunction "VSS_PAD_P$82") (pintype "bidirectional"))
      (node (ref "U1") (pin "P$83") (pinfunction "VSS_PAD_P$83") (pintype "bidirectional"))
      (node (ref "U1") (pin "P$84") (pinfunction "VSS_PAD_P$84") (pintype "bidirectional"))
      (node (ref "U1") (pin "P$85") (pinfunction "VSS_PAD_P$85") (pintype "bidirectional"))
      (node (ref "U1") (pin "P$86") (pinfunction "VSS_PAD_P$86") (pintype "bidirectional"))
      (node (ref "U1") (pin "P$87") (pinfunction "VSS_PAD_P$87") (pintype "bidirectional"))
      (node (ref "U1") (pin "P$88") (pinfunction "VSS_PAD_P$88") (pintype "bidirectional"))
      (node (ref "U1") (pin "P$89") (pinfunction "VSS_PAD_P$89") (pintype "bidirectional"))
      (node (ref "U1") (pin "P$90") (pinfunction "VSS_PAD_P$90") (pintype "bidirectional"))
      (node (ref "U1") (pin "P$B7") (pinfunction "VSS_P$B7") (pintype "power_in"))
      (node (ref "U1") (pin "P$F23") (pinfunction "VSS_PA_P$F23") (pintype "bidirectional"))
      (node (ref "U3") (pin "1") (pinfunction "CTG_1") (pintype "power_in"))
      (node (ref "U3") (pin "4") (pinfunction "GND_4") (pintype "power_in"))
      (node (ref "U3") (pin "6") (pinfunction "QSTRT_6") (pintype "input"))
      (node (ref "U3") (pin "9") (pinfunction "EP_9") (pintype "power_in"))
      (node (ref "X1") (pin "2") (pinfunction "2_2") (pintype "passive"))
      (node (ref "X1") (pin "4") (pinfunction "4_4") (pintype "passive"))
    )
    (net (code "22") (name "HAPTIC_EN{slash}1.4C") (class "Default")
      (node (ref "IC2") (pin "A1") (pinfunction "EN_A1") (pintype "bidirectional"))
    )
    (net (code "23") (name "HAPTIC_EN{slash}2.6A") (class "Default")
      (node (ref "U1") (pin "P$U1") (pinfunction "P0.12_P$U1") (pintype "bidirectional"))
    )
    (net (code "24") (name "IMU_INT1") (class "Default")
      (node (ref "IC3") (pin "5") (pinfunction "INT1_5") (pintype "bidirectional"))
      (node (ref "U1") (pin "P$N1") (pinfunction "P0.08_P$N1") (pintype "bidirectional"))
    )
    (net (code "25") (name "IMU_INT2") (class "Default")
      (node (ref "IC3") (pin "6") (pinfunction "INT2_6") (pintype "bidirectional"))
      (node (ref "U1") (pin "P$P2") (pinfunction "P1.08_P$P2") (pintype "bidirectional"))
    )
    (net (code "26") (name "LX1") (class "Default")
      (node (ref "IC9") (pin "B2") (pinfunction "SW1_1_B2") (pintype "bidirectional"))
      (node (ref "L7") (pin "1") (pinfunction "1_1") (pintype "bidirectional"))
    )
    (net (code "27") (name "LX2") (class "Default")
      (node (ref "IC9") (pin "D2") (pinfunction "SW2_1_D2") (pintype "bidirectional"))
      (node (ref "IC9") (pin "D3") (pinfunction "SW2_2_D3") (pintype "bidirectional"))
      (node (ref "L7") (pin "2") (pinfunction "2_2") (pintype "bidirectional"))
    )
    (net (code "28") (name "MOSI{slash}1.5B") (class "Default")
      (node (ref "J1") (pin "14") (pinfunction "14_14") (pintype "bidirectional"))
    )
    (net (code "29") (name "MOSI{slash}2.2D") (class "Default")
      (node (ref "U1") (pin "P$B13") (pinfunction "P0.03/AIN1_P$B13") (pintype "bidirectional"))
    )
    (net (code "30") (name "N$3") (class "Default")
      (node (ref "C6") (pin "1") (pinfunction "1_1") (pintype "passive"))
      (node (ref "U1") (pin "P$W1") (pinfunction "VDD_P$W1") (pintype "power_in"))
      (node (ref "U1") (pin "P$Y2") (pinfunction "VDDH_P$Y2") (pintype "power_in"))
    )
    (net (code "31") (name "Net-(ANT1-FEED)") (class "Default")
      (node (ref "ANT1") (pin "1") (pinfunction "FEED_1") (pintype "input"))
      (node (ref "C22") (pin "1") (pinfunction "1_1") (pintype "passive"))
      (node (ref "C4") (pin "1") (pinfunction "1_1") (pintype "passive"))
      (node (ref "L1") (pin "2") (pinfunction "2_2") (pintype "passive"))
    )
    (net (code "32") (name "Net-(D2-K)") (class "Default")
      (node (ref "C2-EP-DR") (pin "1") (pinfunction "1_1") (pintype "passive"))
      (node (ref "D2") (pin "1") (pinfunction "K_1") (pintype "bidirectional"))
      (node (ref "D4") (pin "2") (pinfunction "A_2") (pintype "bidirectional"))
    )
    (net (code "33") (name "Net-(D5-A)") (class "Default")
      (node (ref "C2-EP-DR") (pin "2") (pinfunction "2_2") (pintype "passive"))
      (node (ref "D5") (pin "2") (pinfunction "A_2") (pintype "bidirectional"))
      (node (ref "L5") (pin "2") (pinfunction "2_2") (pintype "passive"))
      (node (ref "Q3") (pin "3") (pinfunction "D_3") (pintype "bidirectional"))
    )
    (net (code "34") (name "Net-(EPD_C1-Pad2)") (class "Default")
      (node (ref "EPD_C1") (pin "2") (pinfunction "2_2") (pintype "passive"))
      (node (ref "J1") (pin "5") (pinfunction "5_5") (pintype "bidirectional"))
    )
    (net (code "35") (name "Net-(EPD_C2-Pad2)") (class "Default")
      (node (ref "EPD_C2") (pin "2") (pinfunction "2_2") (pintype "passive"))
      (node (ref "J1") (pin "4") (pinfunction "4_4") (pintype "bidirectional"))
    )
    (net (code "36") (name "Net-(EPD_C6-Pad2)") (class "Default")
      (node (ref "EPD_C6") (pin "2") (pinfunction "2_2") (pintype "passive"))
      (node (ref "J1") (pin "18") (pinfunction "18_18") (pintype "bidirectional"))
    )
    (net (code "37") (name "Net-(EPD_C7-Pad2)") (class "Default")
      (node (ref "EPD_C7") (pin "2") (pinfunction "2_2") (pintype "passive"))
      (node (ref "J1") (pin "19") (pinfunction "19_19") (pintype "bidirectional"))
    )
    (net (code "38") (name "Net-(EPD_C8-Pad2)") (class "Default")
      (node (ref "EPD_C8") (pin "2") (pinfunction "2_2") (pintype "passive"))
      (node (ref "J1") (pin "20") (pinfunction "20_20") (pintype "bidirectional"))
    )
    (net (code "39") (name "Net-(EPD_C10-Pad2)") (class "Default")
      (node (ref "EPD_C10") (pin "2") (pinfunction "2_2") (pintype "passive"))
      (node (ref "J1") (pin "22") (pinfunction "22_22") (pintype "bidirectional"))
    )
    (net (code "40") (name "Net-(EPD_C12-Pad2)") (class "Default")
      (node (ref "EPD_C12") (pin "2") (pinfunction "2_2") (pintype "passive"))
      (node (ref "J1") (pin "24") (pinfunction "24_24") (pintype "bidirectional"))
    )
    (net (code "41") (name "Net-(IC1-TS{slash}MR)") (class "Default")
      (node (ref "IC1") (pin "D1") (pinfunction "TS/MR_D1") (pintype "bidirectional"))
      (node (ref "R9") (pin "2") (pinfunction "2_2") (pintype "bidirectional"))
    )
    (net (code "42") (name "Net-(IC2-REG)") (class "Default")
      (node (ref "C32") (pin "1") (pinfunction "1_1") (pintype "passive"))
      (node (ref "IC2") (pin "A2") (pinfunction "REG_A2") (pintype "bidirectional"))
    )
    (net (code "43") (name "Net-(IC3-SDO)") (class "Default")
      (node (ref "IC3") (pin "1") (pinfunction "SDO_1") (pintype "bidirectional"))
      (node (ref "R3") (pin "2") (pinfunction "2_2") (pintype "bidirectional"))
    )
    (net (code "44") (name "Net-(IC9-SCL)") (class "Default")
      (node (ref "IC9") (pin "D1") (pinfunction "SCL_D1") (pintype "bidirectional"))
      (node (ref "R4") (pin "2") (pinfunction "2_2") (pintype "bidirectional"))
    )
    (net (code "45") (name "Net-(IC9-SDA)") (class "Default")
      (node (ref "IC9") (pin "E1") (pinfunction "SDA_E1") (pintype "bidirectional"))
      (node (ref "R2") (pin "2") (pinfunction "2_2") (pintype "bidirectional"))
    )
    (net (code "46") (name "Net-(J4-CC1)") (class "Default")
      (node (ref "J4") (pin "A5") (pinfunction "CC1_A5") (pintype "bidirectional"))
      (node (ref "R1_USB") (pin "2") (pinfunction "2_2") (pintype "bidirectional"))
    )
    (net (code "47") (name "Net-(J4-CC2)") (class "Default")
      (node (ref "J4") (pin "B5") (pinfunction "CC2_B5") (pintype "bidirectional"))
      (node (ref "R2_USB") (pin "1") (pinfunction "1_1") (pintype "bidirectional"))
    )
    (net (code "48") (name "Net-(L2-Pad2)") (class "Default")
      (node (ref "L2") (pin "2") (pinfunction "2_2") (pintype "passive"))
      (node (ref "L3") (pin "1") (pinfunction "1_1") (pintype "passive"))
    )
    (net (code "49") (name "Net-(R1_EP_DR-Pad1)") (class "Default")
      (node (ref "R1_EP_DR") (pin "1") (pinfunction "1_1") (pintype "bidirectional"))
      (node (ref "R_TYPE_SEL") (pin "2") (pinfunction "2_2") (pintype "bidirectional"))
      (node (ref "SJ1") (pin "2") (pinfunction "2_2") (pintype "passive"))
    )
    (net (code "50") (name "Net-(U1-ANT)") (class "Default")
      (node (ref "C3") (pin "1") (pinfunction "1_1") (pintype "passive"))
      (node (ref "L1") (pin "1") (pinfunction "1_1") (pintype "passive"))
      (node (ref "U1") (pin "P$H23") (pinfunction "ANT_P$H23") (pintype "bidirectional"))
    )
    (net (code "51") (name "Net-(U1-DCC)") (class "Default")
      (node (ref "L2") (pin "1") (pinfunction "1_1") (pintype "passive"))
      (node (ref "U1") (pin "P$B3") (pinfunction "DCC_P$B3") (pintype "output"))
    )
    (net (code "52") (name "Net-(U1-DEC1)") (class "Default")
      (node (ref "C5") (pin "2") (pinfunction "2_2") (pintype "passive"))
      (node (ref "U1") (pin "P$C1") (pinfunction "DEC1_P$C1") (pintype "power_in"))
    )
    (net (code "53") (name "Net-(U1-DEC2)") (class "Default")
      (node (ref "C13") (pin "1") (pinfunction "1_1") (pintype "passive"))
      (node (ref "U1") (pin "P$A18") (pinfunction "DEC2_P$A18") (pintype "bidirectional"))
    )
    (net (code "54") (name "Net-(U1-DEC3)") (class "Default")
      (node (ref "C11") (pin "1") (pinfunction "1_1") (pintype "passive"))
      (node (ref "U1") (pin "P$D23") (pinfunction "DEC3_P$D23") (pintype "bidirectional"))
    )
    (net (code "55") (name "Net-(U1-DEC3V3)") (class "Default")
      (node (ref "C20") (pin "1") (pinfunction "1_1") (pintype "passive"))
      (node (ref "U1") (pin "P$AC5") (pinfunction "DEC3V3_P$AC5") (pintype "bidirectional"))
    )
    (net (code "56") (name "Net-(U1-DEC4)") (class "Default")
      (node (ref "C10") (pin "1") (pinfunction "1_1") (pintype "passive"))
      (node (ref "C15") (pin "1") (pinfunction "1_1") (pintype "passive"))
      (node (ref "C16") (pin "1") (pinfunction "1_1") (pintype "passive"))
      (node (ref "L3") (pin "2") (pinfunction "2_2") (pintype "passive"))
      (node (ref "U1") (pin "P$B5") (pinfunction "DEC4_P$B5") (pintype "power_in"))
      (node (ref "U1") (pin "P$E24") (pinfunction "DEC6_P$E24") (pintype "bidirectional"))
    )
    (net (code "57") (name "Net-(U1-DEC5)") (class "Default")
      (node (ref "C9") (pin "1") (pinfunction "1_1") (pintype "passive"))
      (node (ref "U1") (pin "P$N24") (pinfunction "DEC5_P$N24") (pintype "bidirectional"))
    )
    (net (code "58") (name "Net-(U1-P0.00{slash}XL1)") (class "Default")
      (node (ref "C17") (pin "2") (pinfunction "2_2") (pintype "passive"))
      (node (ref "U1") (pin "P$D2") (pinfunction "P0.00/XL1_P$D2") (pintype "bidirectional"))
      (node (ref "X2") (pin "1") (pinfunction "1_1") (pintype "passive"))
    )
    (net (code "59") (name "Net-(U1-P0.01{slash}XL2)") (class "Default")
      (node (ref "C18") (pin "2") (pinfunction "2_2") (pintype "passive"))
      (node (ref "U1") (pin "P$F2") (pinfunction "P0.01/XL2_P$F2") (pintype "bidirectional"))
      (node (ref "X2") (pin "2") (pinfunction "2_2") (pintype "passive"))
    )
    (net (code "60") (name "Net-(U1-XC1)") (class "Default")
      (node (ref "C1") (pin "1") (pinfunction "1_1") (pintype "passive"))
      (node (ref "U1") (pin "P$B24") (pinfunction "XC1_P$B24") (pintype "input"))
      (node (ref "X1") (pin "1") (pinfunction "1_1") (pintype "passive"))
    )
    (net (code "61") (name "Net-(U1-XC2)") (class "Default")
      (node (ref "C2") (pin "1") (pinfunction "1_1") (pintype "passive"))
      (node (ref "U1") (pin "P$A23") (pinfunction "XC2_P$A23") (pintype "output"))
      (node (ref "X1") (pin "3") (pinfunction "3_3") (pintype "passive"))
    )
    (net (code "62") (name "OUT+") (class "Default")
      (node (ref "IC2") (pin "A3") (pinfunction "OUT+_A3") (pintype "bidirectional"))
      (node (ref "TP_OP") (pin "TP") (pinfunction "TP_TP") (pintype "input"))
    )
    (net (code "63") (name "OUT-") (class "Default")
      (node (ref "IC2") (pin "C3") (pinfunction "OUT-_C3") (pintype "bidirectional"))
      (node (ref "TP_ON") (pin "TP") (pinfunction "TP_TP") (pintype "input"))
    )
    (net (code "64") (name "P0.04") (class "Default")
      (node (ref "U1") (pin "P$J1") (pinfunction "P0.04/AIN2_P$J1") (pintype "bidirectional"))
    )
    (net (code "65") (name "P0.09") (class "Default")
      (node (ref "U1") (pin "P$L24") (pinfunction "P0.09/NFC1_P$L24") (pintype "bidirectional"))
    )
    (net (code "66") (name "P0.13{slash}1.5D") (class "Default")
      (node (ref "C30") (pin "1") (pinfunction "1_1") (pintype "passive"))
      (node (ref "R5") (pin "1") (pinfunction "1_1") (pintype "bidirectional"))
      (node (ref "SW_UP") (pin "2") (pinfunction "2_2") (pintype "passive"))
    )
    (net (code "67") (name "P0.13{slash}2.6C") (class "Default")
      (node (ref "U1") (pin "P$AD8") (pinfunction "P0.13_P$AD8") (pintype "bidirectional"))
    )
    (net (code "68") (name "P0.14{slash}1.5D") (class "Default")
      (node (ref "C31") (pin "1") (pinfunction "1_1") (pintype "passive"))
      (node (ref "R8") (pin "1") (pinfunction "1_1") (pintype "bidirectional"))
      (node (ref "SW_ENT") (pin "2") (pinfunction "2_2") (pintype "passive"))
    )
    (net (code "69") (name "P0.14{slash}2.7C") (class "Default")
      (node (ref "U1") (pin "P$AC9") (pinfunction "P0.14_P$AC9") (pintype "bidirectional"))
    )
    (net (code "70") (name "P0.19") (class "Default")
      (node (ref "U1") (pin "P$AC15") (pinfunction "P0.19_P$AC15") (pintype "bidirectional"))
    )
    (net (code "71") (name "P0.20") (class "Default")
      (node (ref "U1") (pin "P$AD16") (pinfunction "P0.20_P$AD16") (pintype "bidirectional"))
    )
    (net (code "72") (name "P0.21") (class "Default")
      (node (ref "U1") (pin "P$AC17") (pinfunction "P0.21_P$AC17") (pintype "bidirectional"))
    )
    (net (code "73") (name "P0.22") (class "Default")
      (node (ref "U1") (pin "P$AD18") (pinfunction "P0.22_P$AD18") (pintype "bidirectional"))
    )
    (net (code "74") (name "P0.23") (class "Default")
      (node (ref "U1") (pin "P$AC19") (pinfunction "P0.23_P$AC19") (pintype "bidirectional"))
    )
    (net (code "75") (name "P0.24") (class "Default")
      (node (ref "U1") (pin "P$AD20") (pinfunction "P0.24_P$AD20") (pintype "bidirectional"))
    )
    (net (code "76") (name "P0.25") (class "Default")
      (node (ref "U1") (pin "P$AC21") (pinfunction "P0.25_P$AC21") (pintype "bidirectional"))
    )
    (net (code "77") (name "P0.26") (class "Default")
      (node (ref "U1") (pin "P$G1") (pinfunction "P0.26_P$G1") (pintype "bidirectional"))
    )
    (net (code "78") (name "P0.27") (class "Default")
      (node (ref "U1") (pin "P$H2") (pinfunction "P0.27_P$H2") (pintype "bidirectional"))
    )
    (net (code "79") (name "P0.28") (class "Default")
      (node (ref "U1") (pin "P$B11") (pinfunction "P0.28/AIN4_P$B11") (pintype "bidirectional"))
    )
    (net (code "80") (name "P0.29") (class "Default")
      (node (ref "U1") (pin "P$A10") (pinfunction "P0.29/AIN5_P$A10") (pintype "bidirectional"))
    )
    (net (code "81") (name "P0.30") (class "Default")
      (node (ref "U1") (pin "P$B9") (pinfunction "P0.30/AIN6_P$B9") (pintype "bidirectional"))
    )
    (net (code "82") (name "P0.31") (class "Default")
      (node (ref "U1") (pin "P$A8") (pinfunction "P0.31/AIN7_P$A8") (pintype "bidirectional"))
    )
    (net (code "83") (name "P1.01{slash}1.6C") (class "Default")
      (node (ref "Q1") (pin "1") (pinfunction "G_1") (pintype "bidirectional"))
      (node (ref "R_PWR_EPD") (pin "1") (pinfunction "1_1") (pintype "bidirectional"))
    )
    (net (code "84") (name "P1.01{slash}2.4B") (class "Default")
      (node (ref "U1") (pin "P$Y23") (pinfunction "P1.01_P$Y23") (pintype "bidirectional"))
    )
    (net (code "85") (name "P1.02{slash}1.6C") (class "Default")
      (node (ref "C29") (pin "1") (pinfunction "1_1") (pintype "passive"))
      (node (ref "R7") (pin "1") (pinfunction "1_1") (pintype "bidirectional"))
      (node (ref "SW_DN") (pin "2") (pinfunction "2_2") (pintype "passive"))
    )
    (net (code "86") (name "P1.02{slash}2.8C") (class "Default")
      (node (ref "U1") (pin "P$W24") (pinfunction "P1.02_P$W24") (pintype "bidirectional"))
    )
    (net (code "87") (name "P1.03") (class "Default")
      (node (ref "U1") (pin "P$V23") (pinfunction "P1.03_P$V23") (pintype "bidirectional"))
    )
    (net (code "88") (name "P1.04") (class "Default")
      (node (ref "U1") (pin "P$U24") (pinfunction "P1.04_P$U24") (pintype "bidirectional"))
    )
    (net (code "89") (name "P1.05") (class "Default")
      (node (ref "U1") (pin "P$T23") (pinfunction "P1.05_P$T23") (pintype "bidirectional"))
    )
    (net (code "90") (name "P1.07") (class "Default")
      (node (ref "U1") (pin "P$P23") (pinfunction "P1.07_P$P23") (pintype "bidirectional"))
    )
    (net (code "91") (name "P1.09") (class "Default")
      (node (ref "U1") (pin "P$R1") (pinfunction "P1.09_P$R1") (pintype "bidirectional"))
    )
    (net (code "92") (name "P1.10") (class "Default")
      (node (ref "U1") (pin "P$A20") (pinfunction "P1.10_P$A20") (pintype "bidirectional"))
    )
    (net (code "93") (name "P1.11") (class "Default")
      (node (ref "U1") (pin "P$B19") (pinfunction "P1.11_P$B19") (pintype "bidirectional"))
    )
    (net (code "94") (name "P1.12") (class "Default")
      (node (ref "U1") (pin "P$B17") (pinfunction "P1.12_P$B17") (pintype "bidirectional"))
    )
    (net (code "95") (name "P1.13") (class "Default")
      (node (ref "U1") (pin "P$A16") (pinfunction "P1.13_P$A16") (pintype "bidirectional"))
    )
    (net (code "96") (name "P1.14") (class "Default")
      (node (ref "U1") (pin "P$B15") (pinfunction "P1.14_P$B15") (pintype "bidirectional"))
    )
    (net (code "97") (name "P1.15") (class "Default")
      (node (ref "U1") (pin "P$A14") (pinfunction "P1.15_P$A14") (pintype "bidirectional"))
    )
    (net (code "98") (name "P1{slash}06") (class "Default")
      (node (ref "U1") (pin "P$R24") (pinfunction "P1.06_P$R24") (pintype "bidirectional"))
    )
    (net (code "99") (name "PMIC_INT") (class "Default")
      (node (ref "IC1") (pin "A1") (pinfunction "~{INT}_A1") (pintype "bidirectional"))
      (node (ref "U1") (pin "P$T2") (pinfunction "P0.11_P$T2") (pintype "bidirectional"))
    )
    (net (code "100") (name "PREVGH") (class "Default")
      (node (ref "D5") (pin "1") (pinfunction "K_1") (pintype "bidirectional"))
      (node (ref "EPD_C11") (pin "2") (pinfunction "2_2") (pintype "passive"))
      (node (ref "J1") (pin "23") (pinfunction "23_23") (pintype "bidirectional"))
    )
    (net (code "101") (name "PREVGL") (class "Default")
      (node (ref "D2") (pin "2") (pinfunction "A_2") (pintype "bidirectional"))
      (node (ref "EPD_C9") (pin "2") (pinfunction "2_2") (pintype "passive"))
      (node (ref "J1") (pin "21") (pinfunction "21_21") (pintype "bidirectional"))
    )
    (net (code "102") (name "RESE") (class "Default")
      (node (ref "J1") (pin "3") (pinfunction "3_3") (pintype "bidirectional"))
      (node (ref "Q3") (pin "2") (pinfunction "S_2") (pintype "bidirectional"))
      (node (ref "R1_EP_DR") (pin "2") (pinfunction "2_2") (pintype "bidirectional"))
    )
    (net (code "103") (name "RESET") (class "Default")
      (node (ref "J2") (pin "6") (pinfunction "6_6") (pintype "bidirectional"))
      (node (ref "TP_RESET") (pin "TP") (pinfunction "TP_TP") (pintype "input"))
      (node (ref "U1") (pin "P$AC13") (pinfunction "P0.18/RESET_P$AC13") (pintype "bidirectional"))
    )
    (net (code "104") (name "SCK{slash}1.5B") (class "Default")
      (node (ref "J1") (pin "13") (pinfunction "13_13") (pintype "bidirectional"))
    )
    (net (code "105") (name "SCK{slash}2.2D") (class "Default")
      (node (ref "U1") (pin "P$A12") (pinfunction "P0.02/AIN0_P$A12") (pintype "bidirectional"))
    )
    (net (code "106") (name "SCL{slash}1.4C") (class "Default")
      (node (ref "IC2") (pin "C1") (pinfunction "SCL_C1") (pintype "bidirectional"))
      (node (ref "U3") (pin "7") (pinfunction "SCL_7") (pintype "input"))
    )
    (net (code "107") (name "SCL{slash}2.4C") (class "Default")
      (node (ref "IC1") (pin "B1") (pinfunction "SCL_B1") (pintype "bidirectional"))
      (node (ref "IC3") (pin "12") (pinfunction "SCX_12") (pintype "bidirectional"))
      (node (ref "R17") (pin "2") (pinfunction "2_2") (pintype "bidirectional"))
      (node (ref "R4") (pin "1") (pinfunction "1_1") (pintype "bidirectional"))
      (node (ref "TP_SCL") (pin "TP") (pinfunction "TP_TP") (pintype "input"))
      (node (ref "U1") (pin "P$M2") (pinfunction "P0.07_P$M2") (pintype "bidirectional"))
    )
    (net (code "108") (name "SDA{slash}1.4C") (class "Default")
      (node (ref "IC2") (pin "B2") (pinfunction "SDA_B2") (pintype "bidirectional"))
      (node (ref "U3") (pin "8") (pinfunction "SDA_8") (pintype "bidirectional"))
    )
    (net (code "109") (name "SDA{slash}2.4C") (class "Default")
      (node (ref "IC1") (pin "C1") (pinfunction "SDA_C1") (pintype "bidirectional"))
      (node (ref "IC3") (pin "2") (pinfunction "SDX_2") (pintype "bidirectional"))
      (node (ref "R18") (pin "2") (pinfunction "2_2") (pintype "bidirectional"))
      (node (ref "R2") (pin "1") (pinfunction "1_1") (pintype "bidirectional"))
      (node (ref "TP_SDA") (pin "TP") (pinfunction "TP_TP") (pintype "input"))
      (node (ref "U1") (pin "P$L1") (pinfunction "P0.06_P$L1") (pintype "bidirectional"))
    )
    (net (code "110") (name "SWDCLK") (class "Default")
      (node (ref "J2") (pin "4") (pinfunction "4_4") (pintype "bidirectional"))
      (node (ref "TP_SWDCLK") (pin "TP") (pinfunction "TP_TP") (pintype "input"))
      (node (ref "U1") (pin "P$AA24") (pinfunction "SWDCLK_P$AA24") (pintype "input"))
    )
    (net (code "111") (name "SWDIO") (class "Default")
      (node (ref "J2") (pin "2") (pinfunction "2_2") (pintype "bidirectional"))
      (node (ref "TP_SWDIO") (pin "TP") (pinfunction "TP_TP") (pintype "input"))
      (node (ref "U1") (pin "P$AC24") (pinfunction "SWDIO_P$AC24") (pintype "bidirectional"))
    )
    (net (code "112") (name "SWO") (class "Default")
      (node (ref "TP_SWO") (pin "TP") (pinfunction "TP_TP") (pintype "input"))
      (node (ref "U1") (pin "P$AD22") (pinfunction "P1.00_P$AD22") (pintype "bidirectional"))
    )
    (net (code "113") (name "VBAT{slash}1.2A") (class "Default")
      (node (ref "C27") (pin "2") (pinfunction "2_2") (pintype "passive"))
      (node (ref "TP_VBAT") (pin "TP") (pinfunction "TP_TP") (pintype "input"))
      (node (ref "U3") (pin "2") (pinfunction "CELL_2") (pintype "power_in"))
      (node (ref "U3") (pin "3") (pinfunction "VDD_3") (pintype "power_in"))
    )
    (net (code "114") (name "VBAT{slash}2.5C") (class "Default")
      (node (ref "C37") (pin "1") (pinfunction "1_1") (pintype "passive"))
      (node (ref "IC1") (pin "C2") (pinfunction "BAT_C2") (pintype "bidirectional"))
    )
    (net (code "115") (name "VBUS{slash}1.5D") (class "Default")
      (node (ref "C42") (pin "1") (pinfunction "1_1") (pintype "passive"))
      (node (ref "C43") (pin "1") (pinfunction "1_1") (pintype "passive"))
      (node (ref "D3") (pin "5") (pinfunction "VBUS_5") (pintype "bidirectional"))
      (node (ref "J4") (pin "A4_B9") (pinfunction "VBUS_A4_B9") (pintype "power_in"))
      (node (ref "J4") (pin "A9_B4") (pinfunction "VBUS_A9_B4") (pintype "power_in"))
    )
    (net (code "116") (name "VBUS{slash}2.6D") (class "Default")
      (node (ref "C21") (pin "1") (pinfunction "1_1") (pintype "passive"))
      (node (ref "C38") (pin "1") (pinfunction "1_1") (pintype "passive"))
      (node (ref "IC1") (pin "A2") (pinfunction "IN_A2") (pintype "bidirectional"))
      (node (ref "U1") (pin "P$AD2") (pinfunction "VBUS_P$AD2") (pintype "power_in"))
    )
    (net (code "117") (name "VREG") (class "Default")
      (node (ref "C23") (pin "2") (pinfunction "2_2") (pintype "passive"))
      (node (ref "C24") (pin "1") (pinfunction "1_1") (pintype "passive"))
      (node (ref "C39") (pin "1") (pinfunction "1_1") (pintype "passive"))
      (node (ref "IC1") (pin "B2") (pinfunction "SYS_B2") (pintype "bidirectional"))
      (node (ref "IC9") (pin "A1") (pinfunction "EN_A1") (pintype "bidirectional"))
      (node (ref "IC9") (pin "A2") (pinfunction "VIN_1_A2") (pintype "bidirectional"))
      (node (ref "IC9") (pin "A3") (pinfunction "VIN_2_A3") (pintype "bidirectional"))
    )
    (net (code "118") (name "unconnected-(ANT1-NC-Pad2)") (class "Default")
      (node (ref "ANT1") (pin "2") (pinfunction "NC_2") (pintype "no_connect"))
    )
    (net (code "119") (name "unconnected-(IC3-ASCL-Pad11)") (class "Default")
      (node (ref "IC3") (pin "11") (pinfunction "ASCL_11") (pintype "bidirectional"))
    )
    (net (code "120") (name "unconnected-(IC3-ASDA-Pad4)") (class "Default")
      (node (ref "IC3") (pin "4") (pinfunction "ASDA_4") (pintype "bidirectional"))
    )
    (net (code "121") (name "unconnected-(IC9-AGND-PadC1)") (class "Default")
      (node (ref "IC9") (pin "C1") (pinfunction "AGND_C1") (pintype "bidirectional"))
    )
    (net (code "122") (name "unconnected-(IC9-SW1_2-PadB3)") (class "Default")
      (node (ref "IC9") (pin "B3") (pinfunction "SW1_2_B3") (pintype "bidirectional"))
    )
    (net (code "123") (name "unconnected-(J1-Pad1)") (class "Default")
      (node (ref "J1") (pin "1") (pinfunction "1_1") (pintype "bidirectional"))
    )
    (net (code "124") (name "unconnected-(J1-Pad6)") (class "Default")
      (node (ref "J1") (pin "6") (pinfunction "6_6") (pintype "bidirectional"))
    )
    (net (code "125") (name "unconnected-(J1-Pad7)") (class "Default")
      (node (ref "J1") (pin "7") (pinfunction "7_7") (pintype "bidirectional"))
    )
    (net (code "126") (name "unconnected-(J4-SBU1-PadA8)") (class "Default")
      (node (ref "J4") (pin "A8") (pinfunction "SBU1_A8") (pintype "bidirectional"))
    )
    (net (code "127") (name "unconnected-(J4-SBU2-PadB8)") (class "Default")
      (node (ref "J4") (pin "B8") (pinfunction "SBU2_B8") (pintype "bidirectional"))
    )
    (net (code "128") (name "unconnected-(U1-DCCH-PadP$AB2)") (class "Default")
      (node (ref "U1") (pin "P$AB2") (pinfunction "DCCH_P$AB2") (pintype "bidirectional"))
    )
  )
)
